# protect_clamp.net
KiCad netlist of a schematic drawn in EAGLE
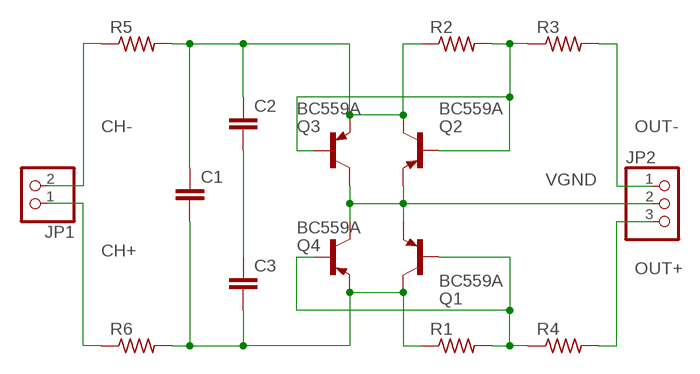
[diagram p0: schematic, sheet 1]

(export (version "E")
  (design (tool "Eeschema 10.0.6"))
  (components
    (comp (ref "C1")
      (value "C2.5/2")
      (footprint "eagle-import:C2.5-2")
      (libsource (lib "eagle-import") (part "C2.5/2"))
    )
    (comp (ref "C2")
      (value "C2.5/2")
      (footprint "eagle-import:C2.5-2")
      (libsource (lib "eagle-import") (part "C2.5/2"))
    )
    (comp (ref "C3")
      (value "C2.5/2")
      (footprint "eagle-import:C2.5-2")
      (libsource (lib "eagle-import") (part "C2.5/2"))
    )
    (comp (ref "JP1")
      (value "PINHD-1X2")
      (footprint "eagle-import:1X02")
      (libsource (lib "eagle-import") (part "PINHD-1X2"))
    )
    (comp (ref "JP2")
      (value "PINHD-1X3")
      (footprint "eagle-import:1X03")
      (libsource (lib "eagle-import") (part "PINHD-1X3"))
    )
    (comp (ref "Q1")
      (value "BC559A")
      (footprint "eagle-import:TO92-EBC")
      (libsource (lib "eagle-import") (part "BC559A"))
    )
    (comp (ref "Q2")
      (value "BC559A")
      (footprint "eagle-import:TO92-EBC")
      (libsource (lib "eagle-import") (part "BC559A"))
    )
    (comp (ref "Q3")
      (value "BC559A")
      (footprint "eagle-import:TO92-EBC")
      (libsource (lib "eagle-import") (part "BC559A"))
    )
    (comp (ref "Q4")
      (value "BC559A")
      (footprint "eagle-import:TO92-EBC")
      (libsource (lib "eagle-import") (part "BC559A"))
    )
    (comp (ref "R1")
      (value "R-US_0204/5")
      (footprint "eagle-import:0204_5")
      (libsource (lib "eagle-import") (part "R-US_0204/5"))
    )
    (comp (ref "R2")
      (value "R-US_0204/5")
      (footprint "eagle-import:0204_5")
      (libsource (lib "eagle-import") (part "R-US_0204/5"))
    )
    (comp (ref "R3")
      (value "R-US_0204/5")
      (footprint "eagle-import:0204_5")
      (libsource (lib "eagle-import") (part "R-US_0204/5"))
    )
    (comp (ref "R4")
      (value "R-US_0204/5")
      (footprint "eagle-import:0204_5")
      (libsource (lib "eagle-import") (part "R-US_0204/5"))
    )
    (comp (ref "R5")
      (value "R-US_0204/5")
      (footprint "eagle-import:0204_5")
      (libsource (lib "eagle-import") (part "R-US_0204/5"))
    )
    (comp (ref "R6")
      (value "R-US_0204/5")
      (footprint "eagle-import:0204_5")
      (libsource (lib "eagle-import") (part "R-US_0204/5"))
    )
  )
  (nets
    (net (code "1") (name "/CH+") (class "Default")
      (node (ref "JP1") (pin "1") (pinfunction "1_1") (pintype "passive"))
      (node (ref "R6") (pin "1") (pinfunction "1_1") (pintype "passive"))
    )
    (net (code "2") (name "/CH-") (class "Default")
      (node (ref "JP1") (pin "2") (pinfunction "2_2") (pintype "passive"))
      (node (ref "R5") (pin "1") (pinfunction "1_1") (pintype "passive"))
    )
    (net (code "3") (name "/OUT+") (class "Default")
      (node (ref "JP2") (pin "3") (pinfunction "3_3") (pintype "passive"))
      (node (ref "R4") (pin "2") (pinfunction "2_2") (pintype "passive"))
    )
    (net (code "4") (name "/OUT-") (class "Default")
      (node (ref "JP2") (pin "1") (pinfunction "1_1") (pintype "passive"))
      (node (ref "R3") (pin "2") (pinfunction "2_2") (pintype "passive"))
    )
    (net (code "5") (name "/VGND") (class "Default")
      (node (ref "JP2") (pin "2") (pinfunction "2_2") (pintype "passive"))
      (node (ref "Q1") (pin "E") (pinfunction "E_E") (pintype "passive"))
      (node (ref "Q2") (pin "E") (pinfunction "E_E") (pintype "passive"))
      (node (ref "Q3") (pin "C") (pinfunction "C_C") (pintype "passive"))
      (node (ref "Q4") (pin "C") (pinfunction "C_C") (pintype "passive"))
    )
    (net (code "6") (name "Net-(C1-Pad1)") (class "Default")
      (node (ref "C1") (pin "1") (pinfunction "1_1") (pintype "passive"))
      (node (ref "C2") (pin "1") (pinfunction "1_1") (pintype "passive"))
      (node (ref "Q2") (pin "C") (pinfunction "C_C") (pintype "passive"))
      (node (ref "Q3") (pin "E") (pinfunction "E_E") (pintype "passive"))
      (node (ref "R2") (pin "1") (pinfunction "1_1") (pintype "passive"))
      (node (ref "R5") (pin "2") (pinfunction "2_2") (pintype "passive"))
    )
    (net (code "7") (name "Net-(C1-Pad2)") (class "Default")
      (node (ref "C1") (pin "2") (pinfunction "2_2") (pintype "passive"))
      (node (ref "C3") (pin "2") (pinfunction "2_2") (pintype "passive"))
      (node (ref "Q1") (pin "C") (pinfunction "C_C") (pintype "passive"))
      (node (ref "Q4") (pin "E") (pinfunction "E_E") (pintype "passive"))
      (node (ref "R1") (pin "1") (pinfunction "1_1") (pintype "passive"))
      (node (ref "R6") (pin "2") (pinfunction "2_2") (pintype "passive"))
    )
    (net (code "8") (name "Net-(C2-Pad2)") (class "Default")
      (node (ref "C2") (pin "2") (pinfunction "2_2") (pintype "passive"))
      (node (ref "C3") (pin "1") (pinfunction "1_1") (pintype "passive"))
    )
    (net (code "9") (name "Net-(Q1-PadB)") (class "Default")
      (node (ref "Q1") (pin "B") (pinfunction "B_B") (pintype "passive"))
      (node (ref "Q4") (pin "B") (pinfunction "B_B") (pintype "passive"))
      (node (ref "R1") (pin "2") (pinfunction "2_2") (pintype "passive"))
      (node (ref "R4") (pin "1") (pinfunction "1_1") (pintype "passive"))
    )
    (net (code "10") (name "Net-(Q2-PadB)") (class "Default")
      (node (ref "Q2") (pin "B") (pinfunction "B_B") (pintype "passive"))
      (node (ref "Q3") (pin "B") (pinfunction "B_B") (pintype "passive"))
      (node (ref "R2") (pin "2") (pinfunction "2_2") (pintype "passive"))
      (node (ref "R3") (pin "1") (pinfunction "1_1") (pintype "passive"))
    )
  )
)
